# USB_UART.net
KiCad netlist of a schematic drawn in Altium Designer
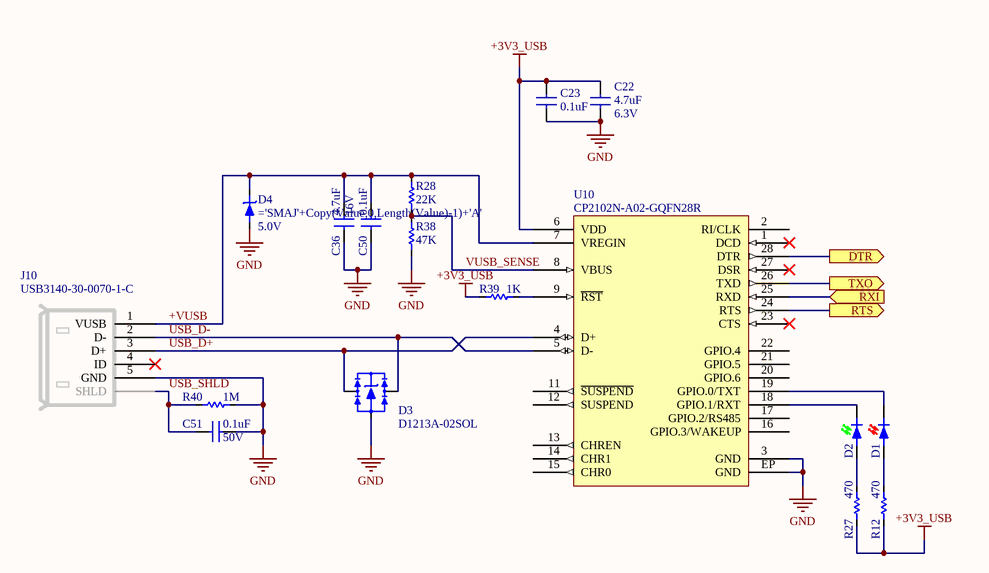
[diagram p0: USB_UART.SchDoc]

(export (version "E")
  (design (tool "Eeschema 10.0.6"))
  (components
    (comp (ref "C22")
      (value "4.7uF")
      (footprint "0603_Capacitor")
      (description "CAP CER 4.7UF 6.3V X5R 0603")
      (fields (field (name "VOLTAGE") "6.3V") (field (name "Comment") "CAP 4.7uF 6.3V X5R"))
      (libsource (lib "capacitor") (part "C_0603_4.7uF_6.3V_10%"))
    )
    (comp (ref "C23")
      (value "0.1uF")
      (footprint "0402_CAPACITOR")
      (description "CAP CERM 0.1uF 10% 16V 0402")
      (fields (field (name "VOLTAGE") "16V") (field (name "Comment") "CAP 0.1uF 16V X7R"))
      (libsource (lib "capacitor") (part "C_0402_0.1uF_16V_10%"))
    )
    (comp (ref "C36")
      (value "4.7uF")
      (footprint "0805_Capacitor")
      (description "CAP CERM 4.7uF 10% 16V 0805")
      (fields
        (field (name "VOLTAGE") "16V")
        (field (name "Comment") "CAP 4.7uF 16V X5R")
        (field (name "SVP CREATOR") "Spencer Berglund")
      )
      (libsource (lib "capacitor") (part "C_0805_4.7uF_16V_10%"))
    )
    (comp (ref "C50")
      (value "0.1uF")
      (footprint "0402_CAPACITOR")
      (description "CAP CERM 0.1uF 10% 16V 0402")
      (fields (field (name "VOLTAGE") "16V") (field (name "Comment") "CAP 0.1uF 16V X7R"))
      (libsource (lib "capacitor") (part "C_0402_0.1uF_16V_10%"))
    )
    (comp (ref "C51")
      (value "0.1uF")
      (footprint "0603_CAPACITOR")
      (description "CAP CERM 0.1uF 10% 50V 0603")
      (fields
        (field (name "VOLTAGE") "50V")
        (field (name "Comment") "CAP 0.1uF 50V X7R")
        (field (name "SVP CREATOR") "Spencer Berglund")
      )
      (libsource (lib "capacitor") (part "C_0603_0.1uF_50V_10%"))
    )
    (comp (ref "D1")
      (value "LTST-C194KRKT")
      (footprint "0603_LED_Red")
      (description "Red 631nm LED Indication - Discrete 2V 0603 (1608 Metric)")
      (fields (field (name "MANUFACTURER") "Vishay Lite-On"))
      (libsource (lib "diode") (part "D_LED_0603_Red"))
    )
    (comp (ref "D2")
      (value "LTST-C194KGKT")
      (footprint "0603_LED_Green")
      (description "Green 572nm LED Indication - Discrete 2.1V 0603 (1608 Metric)")
      (fields (field (name "MANUFACTURER") "Vishay Lite-On"))
      (libsource (lib "diode") (part "D_LED_0603_Green"))
    )
    (comp (ref "D3")
      (value "D1213A-02SOL")
      (footprint "SOT23-3")
      (description "10V (Typ) Clamp 1A (8/20µs) Ipp Tvs Diode Surface Mount SOT-23 (for USB)")
      (fields (field (name "MANUFACTURER") "Diodes Incorporated"))
      (libsource (lib "diode") (part "D_D1213A-02SOL"))
    )
    (comp (ref "D4")
      (value "5.0V")
      (footprint "SMA")
      (description "SMA Unidirectional TVS Diode")
      (fields
        (field (name "MANUFACTURER") "Vishay")
        (field (name "MANUFACTURER PN") "SMAJA")
        (field (name "Comment") "TVS Diode")
      )
      (libsource (lib "diode") (part "D_TVS_SMAJ_Uni_generic"))
    )
    (comp (ref "J10")
      (value "USB3140-30-0070-1-C")
      (footprint "J_USB3140-30-0070-1-C")
      (description "USB - micro B USB 2.0 Receptacle Connector 5 Position Surface Mount, Through Hole")
      (libsource (lib "connector") (part "J_USB3140-30-0070-1-C"))
    )
    (comp (ref "R12")
      (value "470")
      (footprint "0402_Resistor")
      (description "Generic 0402 Resistor (10.2R to 10M)")
      (fields (field (name "TOLERANCE") "±1%") (field (name "MANUFACTURER") "Yageo"))
      (libsource (lib "resistor") (part "R_0402_generic_1%"))
    )
    (comp (ref "R27")
      (value "470")
      (footprint "0402_Resistor")
      (description "Generic 0402 Resistor (10.2R to 10M)")
      (fields (field (name "TOLERANCE") "±1%") (field (name "MANUFACTURER") "Yageo"))
      (libsource (lib "resistor") (part "R_0402_generic_1%"))
    )
    (comp (ref "R28")
      (value "22K")
      (footprint "0402_Resistor")
      (description "Generic 0402 Resistor (10.2R to 10M)")
      (fields (field (name "TOLERANCE") "±1%") (field (name "MANUFACTURER") "Yageo"))
      (libsource (lib "resistor") (part "R_0402_generic_1%"))
    )
    (comp (ref "R38")
      (value "47K")
      (footprint "0402_Resistor")
      (description "Generic 0402 Resistor (10.2R to 10M)")
      (fields (field (name "TOLERANCE") "±1%") (field (name "MANUFACTURER") "Yageo"))
      (libsource (lib "resistor") (part "R_0402_generic_1%"))
    )
    (comp (ref "R39")
      (value "1K")
      (footprint "0402_Resistor")
      (description "Generic 0402 Resistor (10.2R to 10M)")
      (fields (field (name "TOLERANCE") "±1%") (field (name "MANUFACTURER") "Yageo"))
      (libsource (lib "resistor") (part "R_0402_generic_1%"))
    )
    (comp (ref "R40")
      (value "1M")
      (footprint "0603_Resistor")
      (description "Generic 0603 Resistor (10.2R to 10M)")
      (fields (field (name "TOLERANCE") "±1%") (field (name "MANUFACTURER") "Yageo"))
      (libsource (lib "resistor") (part "R_0603_generic_1%"))
    )
    (comp (ref "U10")
      (value "CP2102N-A02-GQFN28R")
      (footprint "QFN-28-EP_5x5mm")
      (description "USB Bridge, USB to UART USB 2.0 UART Interface 28-QFN (5x5)")
      (libsource (lib "ic") (part "U_CP2102N-A02-GQFN28R"))
    )
  )
  (nets
    (net (code "1") (name "+3V3_USB") (class "Default")
      (node (ref "C22") (pin "2") (pinfunction "2_2") (pintype "passive"))
      (node (ref "C23") (pin "1") (pinfunction "1_1") (pintype "passive"))
      (node (ref "R12") (pin "2") (pinfunction "2_2") (pintype "passive"))
      (node (ref "R27") (pin "2") (pinfunction "2_2") (pintype "passive"))
      (node (ref "R39") (pin "1") (pinfunction "1_1") (pintype "passive"))
      (node (ref "U10") (pin "6") (pinfunction "VDD_6") (pintype "power_in"))
    )
    (net (code "2") (name "/+VUSB") (class "Default")
      (node (ref "C36") (pin "2") (pinfunction "2_2") (pintype "passive"))
      (node (ref "C50") (pin "1") (pinfunction "1_1") (pintype "passive"))
      (node (ref "D4") (pin "2") (pinfunction "Cathode_2") (pintype "passive"))
      (node (ref "J10") (pin "1") (pinfunction "VUSB_1") (pintype "power_in"))
      (node (ref "R28") (pin "2") (pinfunction "2_2") (pintype "passive"))
      (node (ref "U10") (pin "7") (pinfunction "VREGIN_7") (pintype "power_in"))
    )
    (net (code "3") (name "/DTR") (class "Default")
      (node (ref "U10") (pin "28") (pinfunction "DTR_28") (pintype "output"))
    )
    (net (code "4") (name "/RTS") (class "Default")
      (node (ref "U10") (pin "24") (pinfunction "RTS_24") (pintype "output"))
    )
    (net (code "5") (name "/RXI") (class "Default")
      (node (ref "U10") (pin "25") (pinfunction "RXD_25") (pintype "input"))
    )
    (net (code "6") (name "/TXO") (class "Default")
      (node (ref "U10") (pin "26") (pinfunction "TXD_26") (pintype "output"))
    )
    (net (code "7") (name "/USB_D+") (class "Default")
      (node (ref "D3") (pin "1") (pinfunction "1_1") (pintype "passive"))
      (node (ref "J10") (pin "3") (pinfunction "D+_3") (pintype "passive"))
      (node (ref "U10") (pin "4") (pinfunction "D+_4") (pintype "bidirectional"))
    )
    (net (code "8") (name "/USB_D-") (class "Default")
      (node (ref "D3") (pin "2") (pinfunction "2_2") (pintype "passive"))
      (node (ref "J10") (pin "2") (pinfunction "D-_2") (pintype "passive"))
      (node (ref "U10") (pin "5") (pinfunction "D-_5") (pintype "bidirectional"))
    )
    (net (code "9") (name "/USB_SHLD") (class "Default")
      (node (ref "C51") (pin "2") (pinfunction "2_2") (pintype "passive"))
      (node (ref "J10") (pin "SHLD") (pinfunction "SHLD_SHLD") (pintype "passive"))
      (node (ref "R40") (pin "1") (pinfunction "1_1") (pintype "passive"))
    )
    (net (code "10") (name "/VUSB_SENSE") (class "Default")
      (node (ref "R28") (pin "1") (pinfunction "1_1") (pintype "passive"))
      (node (ref "R38") (pin "2") (pinfunction "2_2") (pintype "passive"))
      (node (ref "U10") (pin "8") (pinfunction "VBUS_8") (pintype "input"))
    )
    (net (code "11") (name "GND") (class "Default")
      (node (ref "C22") (pin "1") (pinfunction "1_1") (pintype "passive"))
      (node (ref "C23") (pin "2") (pinfunction "2_2") (pintype "passive"))
      (node (ref "C36") (pin "1") (pinfunction "1_1") (pintype "passive"))
      (node (ref "C50") (pin "2") (pinfunction "2_2") (pintype "passive"))
      (node (ref "C51") (pin "1") (pinfunction "1_1") (pintype "passive"))
      (node (ref "D3") (pin "3") (pinfunction "3_3") (pintype "passive"))
      (node (ref "D4") (pin "1") (pinfunction "Anode_1") (pintype "passive"))
      (node (ref "J10") (pin "5") (pinfunction "GND_5") (pintype "power_in"))
      (node (ref "R38") (pin "1") (pinfunction "1_1") (pintype "passive"))
      (node (ref "R40") (pin "2") (pinfunction "2_2") (pintype "passive"))
      (node (ref "U10") (pin "3") (pinfunction "GND_3") (pintype "power_in"))
      (node (ref "U10") (pin "EP") (pinfunction "GND_EP") (pintype "power_in"))
    )
    (net (code "12") (name "Net-(D1-Anode)") (class "Default")
      (node (ref "D1") (pin "1") (pinfunction "Anode_1") (pintype "passive"))
      (node (ref "R12") (pin "1") (pinfunction "1_1") (pintype "passive"))
    )
    (net (code "13") (name "Net-(D1-Cathode)") (class "Default")
      (node (ref "D1") (pin "2") (pinfunction "Cathode_2") (pintype "passive"))
      (node (ref "U10") (pin "19") (pinfunction "GPIO.0/TXT_19") (pintype "passive"))
    )
    (net (code "14") (name "Net-(D2-Anode)") (class "Default")
      (node (ref "D2") (pin "1") (pinfunction "Anode_1") (pintype "passive"))
      (node (ref "R27") (pin "1") (pinfunction "1_1") (pintype "passive"))
    )
    (net (code "15") (name "Net-(D2-Cathode)") (class "Default")
      (node (ref "D2") (pin "2") (pinfunction "Cathode_2") (pintype "passive"))
      (node (ref "U10") (pin "18") (pinfunction "GPIO.1/RXT_18") (pintype "passive"))
    )
    (net (code "16") (name "Net-(U10-~{RST})") (class "Default")
      (node (ref "R39") (pin "2") (pinfunction "2_2") (pintype "passive"))
      (node (ref "U10") (pin "9") (pinfunction "~{RST}_9") (pintype "input"))
    )
    (net (code "17") (name "unconnected-(J10-ID-Pad4)") (class "Default")
      (node (ref "J10") (pin "4") (pinfunction "ID_4") (pintype "passive+no_connect"))
    )
    (net (code "18") (name "unconnected-(U10-CHR0-Pad15)") (class "Default")
      (node (ref "U10") (pin "15") (pinfunction "CHR0_15") (pintype "output"))
    )
    (net (code "19") (name "unconnected-(U10-CHR1-Pad14)") (class "Default")
      (node (ref "U10") (pin "14") (pinfunction "CHR1_14") (pintype "output"))
    )
    (net (code "20") (name "unconnected-(U10-CHREN-Pad13)") (class "Default")
      (node (ref "U10") (pin "13") (pinfunction "CHREN_13") (pintype "output"))
    )
    (net (code "21") (name "unconnected-(U10-CTS-Pad23)") (class "Default")
      (node (ref "U10") (pin "23") (pinfunction "CTS_23") (pintype "input+no_connect"))
    )
    (net (code "22") (name "unconnected-(U10-DCD-Pad1)") (class "Default")
      (node (ref "U10") (pin "1") (pinfunction "DCD_1") (pintype "input+no_connect"))
    )
    (net (code "23") (name "unconnected-(U10-DSR-Pad27)") (class "Default")
      (node (ref "U10") (pin "27") (pinfunction "DSR_27") (pintype "input+no_connect"))
    )
    (net (code "24") (name "unconnected-(U10-GPIO.2{slash}RS485-Pad17)") (class "Default")
      (node (ref "U10") (pin "17") (pinfunction "GPIO.2/RS485_17") (pintype "passive"))
    )
    (net (code "25") (name "unconnected-(U10-GPIO.3{slash}WAKEUP-Pad16)") (class "Default")
      (node (ref "U10") (pin "16") (pinfunction "GPIO.3/WAKEUP_16") (pintype "passive"))
    )
    (net (code "26") (name "unconnected-(U10-GPIO.4-Pad22)") (class "Default")
      (node (ref "U10") (pin "22") (pinfunction "GPIO.4_22") (pintype "passive"))
    )
    (net (code "27") (name "unconnected-(U10-GPIO.5-Pad21)") (class "Default")
      (node (ref "U10") (pin "21") (pinfunction "GPIO.5_21") (pintype "passive"))
    )
    (net (code "28") (name "unconnected-(U10-GPIO.6-Pad20)") (class "Default")
      (node (ref "U10") (pin "20") (pinfunction "GPIO.6_20") (pintype "passive"))
    )
    (net (code "29") (name "unconnected-(U10-RI{slash}CLK-Pad2)") (class "Default")
      (node (ref "U10") (pin "2") (pinfunction "RI/CLK_2") (pintype "passive"))
    )
    (net (code "30") (name "unconnected-(U10-SUSPEND-Pad12)") (class "Default")
      (node (ref "U10") (pin "12") (pinfunction "SUSPEND_12") (pintype "output"))
    )
    (net (code "31") (name "unconnected-(U10-~{SUSPEND}-Pad11)") (class "Default")
      (node (ref "U10") (pin "11") (pinfunction "~{SUSPEND}_11") (pintype "output"))
    )
  )
)
